# generation-7-electronics.net
KiCad netlist of a schematic drawn in EAGLE
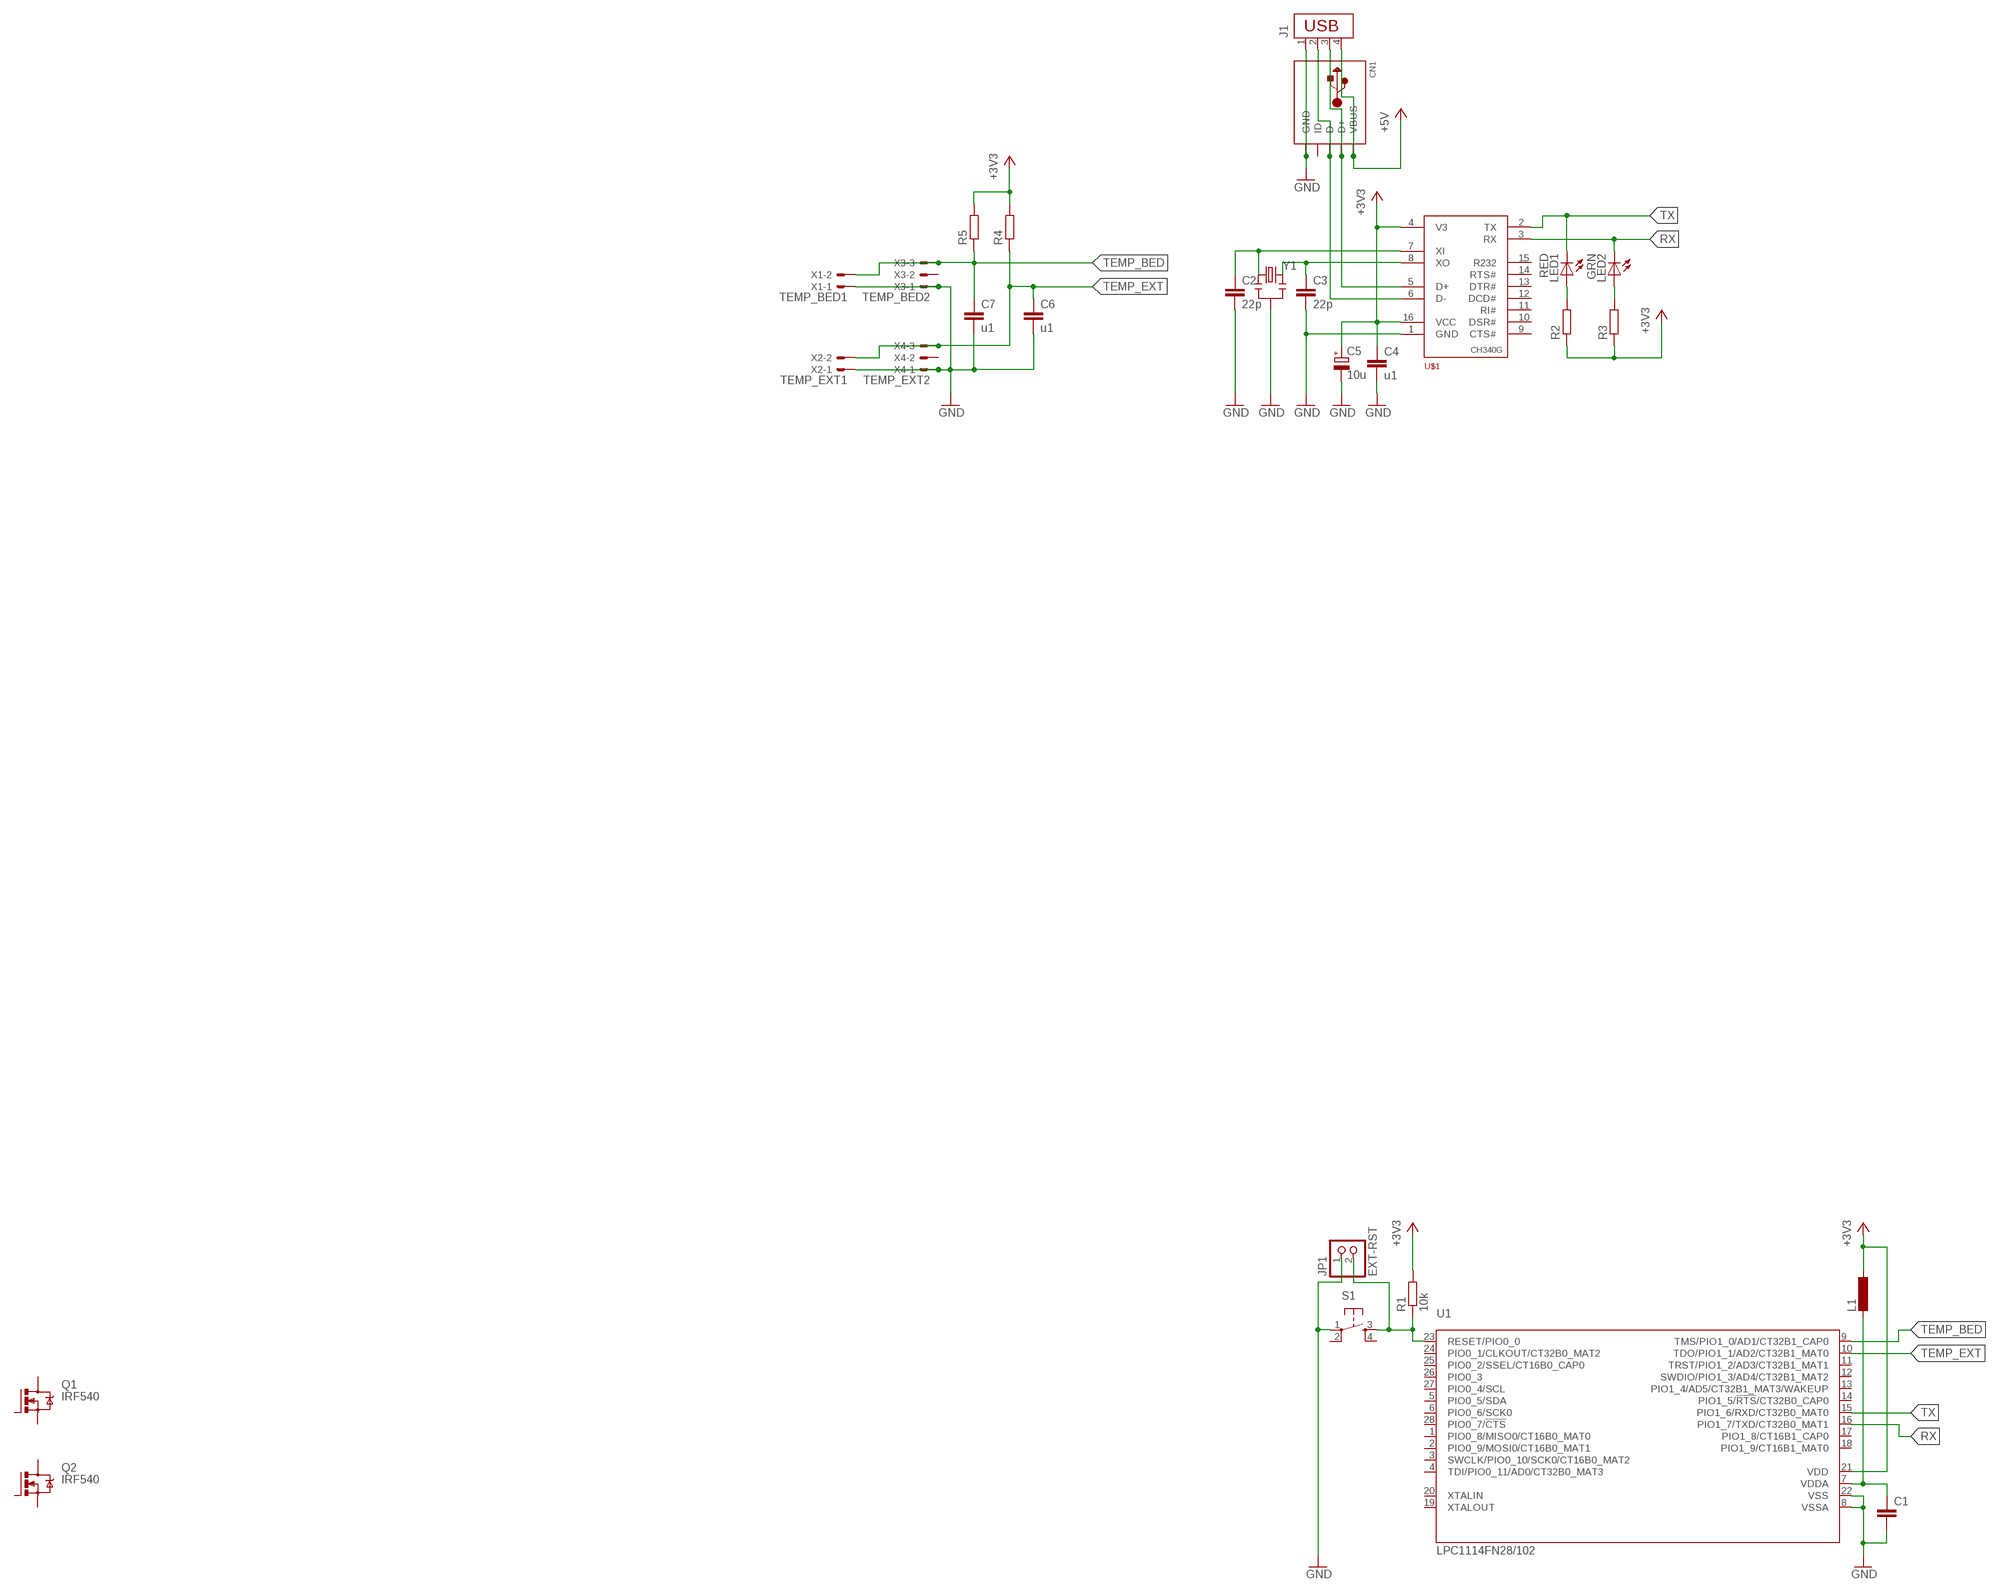
[diagram p0: schematic, sheet 1]

(export (version "E")
  (design (tool "Eeschema 10.0.6"))
  (components
    (comp (ref "C1")
      (value "C-EU025-025X050")
      (footprint "eagle-import:C025-025X050")
      (libsource (lib "eagle-import") (part "C-EU025-025X050"))
    )
    (comp (ref "C2")
      (value "22p")
      (footprint "eagle-import:C025-025X050")
      (libsource (lib "eagle-import") (part "C-EU025-025X050"))
    )
    (comp (ref "C3")
      (value "22p")
      (footprint "eagle-import:C025-025X050")
      (libsource (lib "eagle-import") (part "C-EU025-025X050"))
    )
    (comp (ref "C4")
      (value "u1")
      (footprint "eagle-import:C025-025X050")
      (libsource (lib "eagle-import") (part "C-EU025-025X050"))
    )
    (comp (ref "C5")
      (value "10u")
      (footprint "eagle-import:E2,5-6")
      (libsource (lib "eagle-import") (part "CPOL-EUE2.5-6"))
    )
    (comp (ref "C6")
      (value "u1")
      (footprint "eagle-import:C025-025X050")
      (libsource (lib "eagle-import") (part "C-EU025-025X050"))
    )
    (comp (ref "C7")
      (value "u1")
      (footprint "eagle-import:C025-025X050")
      (libsource (lib "eagle-import") (part "C-EU025-025X050"))
    )
    (comp (ref "CN1")
      (value "USBTHM")
      (footprint "eagle-import:USB-MINIB-THM")
      (libsource (lib "eagle-import") (part "USBTHM"))
    )
    (comp (ref "J1")
      (value "CON-USB-B")
      (footprint "eagle-import:USB-B")
      (libsource (lib "eagle-import") (part "CON-USB-B"))
    )
    (comp (ref "JP1")
      (value "EXT-RST")
      (footprint "eagle-import:1X02")
      (libsource (lib "eagle-import") (part "PINHD-1X2"))
    )
    (comp (ref "L1")
      (value "L-EU0207/2V")
      (footprint "eagle-import:0207_2V")
      (libsource (lib "eagle-import") (part "L-EU0207/2V"))
    )
    (comp (ref "LED1")
      (value "RED")
      (footprint "eagle-import:LED3MM")
      (libsource (lib "eagle-import") (part "LED3MM"))
    )
    (comp (ref "LED2")
      (value "GRN")
      (footprint "eagle-import:LED3MM")
      (libsource (lib "eagle-import") (part "LED3MM"))
    )
    (comp (ref "Q1")
      (value "IRF540")
      (footprint "eagle-import:TO220BV")
      (libsource (lib "eagle-import") (part "IRF540"))
    )
    (comp (ref "Q2")
      (value "IRF540")
      (footprint "eagle-import:TO220BV")
      (libsource (lib "eagle-import") (part "IRF540"))
    )
    (comp (ref "R1")
      (value "10k")
      (footprint "eagle-import:0204_7")
      (libsource (lib "eagle-import") (part "R-EU_0204/7"))
    )
    (comp (ref "R2")
      (value "R-EU_0204/7")
      (footprint "eagle-import:0204_7")
      (libsource (lib "eagle-import") (part "R-EU_0204/7"))
    )
    (comp (ref "R3")
      (value "R-EU_0204/7")
      (footprint "eagle-import:0204_7")
      (libsource (lib "eagle-import") (part "R-EU_0204/7"))
    )
    (comp (ref "R4")
      (value "R-EU_0204/7")
      (footprint "eagle-import:0204_7")
      (libsource (lib "eagle-import") (part "R-EU_0204/7"))
    )
    (comp (ref "R5")
      (value "R-EU_0204/7")
      (footprint "eagle-import:0204_7")
      (libsource (lib "eagle-import") (part "R-EU_0204/7"))
    )
    (comp (ref "S1")
      (value "TAC_SWITCHPTH")
      (footprint "eagle-import:TACTILE-PTH")
      (libsource (lib "eagle-import") (part "TAC_SWITCHPTH"))
    )
    (comp (ref "U$1")
      (value "CH340G")
      (footprint "eagle-import:SO16")
      (libsource (lib "eagle-import") (part "CH340G"))
    )
    (comp (ref "U1")
      (value "LPC1114FN28/102")
      (footprint "eagle-import:SOT117")
      (libsource (lib "eagle-import") (part "LPC1114FN28/102"))
    )
    (comp (ref "X1")
      (value "TEMP_BED1")
      (footprint "eagle-import:JST-XH-02-PACKAGE-LONG-PAD")
      (libsource (lib "eagle-import") (part "JST-XH-02-PIN-LONG-PAD"))
    )
    (comp (ref "X2")
      (value "TEMP_EXT1")
      (footprint "eagle-import:JST-XH-02-PACKAGE-LONG-PAD")
      (libsource (lib "eagle-import") (part "JST-XH-02-PIN-LONG-PAD"))
    )
    (comp (ref "X3")
      (value "TEMP_BED2")
      (footprint "eagle-import:JST-XH-03-PACKAGE-LONG-PAD")
      (libsource (lib "eagle-import") (part "JST-XH-03-PIN-LONG-PAD"))
    )
    (comp (ref "X4")
      (value "TEMP_EXT2")
      (footprint "eagle-import:JST-XH-03-PACKAGE-LONG-PAD")
      (libsource (lib "eagle-import") (part "JST-XH-03-PIN-LONG-PAD"))
    )
    (comp (ref "Y1")
      (value "RESONATORPTH")
      (footprint "eagle-import:RESONATOR-PTH")
      (libsource (lib "eagle-import") (part "RESONATORPTH"))
    )
  )
  (nets
    (net (code "1") (name "+3V3") (class "Default")
      (node (ref "C4") (pin "1") (pinfunction "1_1") (pintype "passive"))
      (node (ref "C5") (pin "+") (pinfunction "+_+") (pintype "passive"))
      (node (ref "L1") (pin "1") (pinfunction "1_1") (pintype "passive"))
      (node (ref "R1") (pin "2") (pinfunction "2_2") (pintype "passive"))
      (node (ref "R2") (pin "1") (pinfunction "1_1") (pintype "passive"))
      (node (ref "R3") (pin "1") (pinfunction "1_1") (pintype "passive"))
      (node (ref "R4") (pin "2") (pinfunction "2_2") (pintype "passive"))
      (node (ref "R5") (pin "2") (pinfunction "2_2") (pintype "passive"))
      (node (ref "U$1") (pin "16") (pinfunction "VCC_16") (pintype "bidirectional"))
      (node (ref "U$1") (pin "4") (pinfunction "V3_4") (pintype "bidirectional"))
      (node (ref "U1") (pin "21") (pinfunction "VDD_21") (pintype "power_in"))
    )
    (net (code "2") (name "+5V") (class "Default")
      (node (ref "CN1") (pin "VBUS") (pinfunction "VBUS_VBUS") (pintype "power_in"))
      (node (ref "J1") (pin "4") (pinfunction "4_4") (pintype "passive"))
    )
    (net (code "3") (name "GND") (class "Default")
      (node (ref "C1") (pin "2") (pinfunction "2_2") (pintype "passive"))
      (node (ref "C2") (pin "2") (pinfunction "2_2") (pintype "passive"))
      (node (ref "C3") (pin "2") (pinfunction "2_2") (pintype "passive"))
      (node (ref "C4") (pin "2") (pinfunction "2_2") (pintype "passive"))
      (node (ref "C5") (pin "-") (pinfunction "-_-") (pintype "passive"))
      (node (ref "C6") (pin "2") (pinfunction "2_2") (pintype "passive"))
      (node (ref "C7") (pin "2") (pinfunction "2_2") (pintype "passive"))
      (node (ref "CN1") (pin "GND") (pinfunction "GND_GND") (pintype "power_in"))
      (node (ref "J1") (pin "1") (pinfunction "1_1") (pintype "passive"))
      (node (ref "JP1") (pin "1") (pinfunction "1_1") (pintype "passive"))
      (node (ref "S1") (pin "1") (pinfunction "1_1") (pintype "passive"))
      (node (ref "U$1") (pin "1") (pinfunction "GND_1") (pintype "bidirectional"))
      (node (ref "U1") (pin "22") (pinfunction "VSS_22") (pintype "power_in"))
      (node (ref "U1") (pin "8") (pinfunction "VSSA_8") (pintype "power_in"))
      (node (ref "X1") (pin "1") (pinfunction "S_1") (pintype "passive"))
      (node (ref "X2") (pin "1") (pinfunction "S_1") (pintype "passive"))
      (node (ref "X3") (pin "1") (pinfunction "S_1") (pintype "passive"))
      (node (ref "X4") (pin "1") (pinfunction "S_1") (pintype "passive"))
      (node (ref "Y1") (pin "2") (pinfunction "2_2") (pintype "passive"))
    )
    (net (code "4") (name "Net-(LED1-PadA)") (class "Default")
      (node (ref "LED1") (pin "A") (pinfunction "A_A") (pintype "passive"))
      (node (ref "R2") (pin "2") (pinfunction "2_2") (pintype "passive"))
    )
    (net (code "5") (name "Net-(LED2-PadA)") (class "Default")
      (node (ref "LED2") (pin "A") (pinfunction "A_A") (pintype "passive"))
      (node (ref "R3") (pin "2") (pinfunction "2_2") (pintype "passive"))
    )
    (net (code "6") (name "Net-(U$1-D+)") (class "Default")
      (node (ref "CN1") (pin "D+") (pinfunction "D+_D+") (pintype "bidirectional"))
      (node (ref "J1") (pin "3") (pinfunction "3_3") (pintype "passive"))
      (node (ref "U$1") (pin "5") (pinfunction "D+_5") (pintype "bidirectional"))
    )
    (net (code "7") (name "Net-(U$1-D-)") (class "Default")
      (node (ref "CN1") (pin "D-") (pinfunction "D-_D-") (pintype "bidirectional"))
      (node (ref "J1") (pin "2") (pinfunction "2_2") (pintype "passive"))
      (node (ref "U$1") (pin "6") (pinfunction "D-_6") (pintype "bidirectional"))
    )
    (net (code "8") (name "Net-(U$1-XI)") (class "Default")
      (node (ref "C2") (pin "1") (pinfunction "1_1") (pintype "passive"))
      (node (ref "U$1") (pin "7") (pinfunction "XI_7") (pintype "bidirectional"))
      (node (ref "Y1") (pin "1") (pinfunction "1_1") (pintype "passive"))
    )
    (net (code "9") (name "Net-(U$1-XO)") (class "Default")
      (node (ref "C3") (pin "1") (pinfunction "1_1") (pintype "passive"))
      (node (ref "U$1") (pin "8") (pinfunction "XO_8") (pintype "bidirectional"))
      (node (ref "Y1") (pin "3") (pinfunction "3_3") (pintype "passive"))
    )
    (net (code "10") (name "Net-(U1-RESET{slash}PIO0_0)") (class "Default")
      (node (ref "JP1") (pin "2") (pinfunction "2_2") (pintype "passive"))
      (node (ref "R1") (pin "1") (pinfunction "1_1") (pintype "passive"))
      (node (ref "S1") (pin "3") (pinfunction "3_3") (pintype "passive"))
      (node (ref "U1") (pin "23") (pinfunction "RESET/PIO0_0_23") (pintype "bidirectional"))
    )
    (net (code "11") (name "Net-(U1-VDDA)") (class "Default")
      (node (ref "C1") (pin "1") (pinfunction "1_1") (pintype "passive"))
      (node (ref "L1") (pin "2") (pinfunction "2_2") (pintype "passive"))
      (node (ref "U1") (pin "7") (pinfunction "VDDA_7") (pintype "power_in"))
    )
    (net (code "12") (name "RX") (class "Default")
      (node (ref "LED2") (pin "K") (pinfunction "C_K") (pintype "passive"))
      (node (ref "U$1") (pin "3") (pinfunction "RX_3") (pintype "bidirectional"))
      (node (ref "U1") (pin "16") (pinfunction "PIO1_7/TXD/CT32B0_MAT1_16") (pintype "bidirectional"))
    )
    (net (code "13") (name "TEMP_BED") (class "Default")
      (node (ref "C7") (pin "1") (pinfunction "1_1") (pintype "passive"))
      (node (ref "R5") (pin "1") (pinfunction "1_1") (pintype "passive"))
      (node (ref "U1") (pin "9") (pinfunction "TMS/PIO1_0/AD1/CT32B1_CAP0_9") (pintype "bidirectional"))
      (node (ref "X1") (pin "2") (pinfunction "S_2") (pintype "passive"))
      (node (ref "X3") (pin "3") (pinfunction "S_3") (pintype "passive"))
    )
    (net (code "14") (name "TEMP_EXT") (class "Default")
      (node (ref "C6") (pin "1") (pinfunction "1_1") (pintype "passive"))
      (node (ref "R4") (pin "1") (pinfunction "1_1") (pintype "passive"))
      (node (ref "U1") (pin "10") (pinfunction "TDO/PIO1_1/AD2/CT32B1_MAT0_10") (pintype "bidirectional"))
      (node (ref "X2") (pin "2") (pinfunction "S_2") (pintype "passive"))
      (node (ref "X4") (pin "3") (pinfunction "S_3") (pintype "passive"))
    )
    (net (code "15") (name "TX") (class "Default")
      (node (ref "LED1") (pin "K") (pinfunction "C_K") (pintype "passive"))
      (node (ref "U$1") (pin "2") (pinfunction "TX_2") (pintype "bidirectional"))
      (node (ref "U1") (pin "15") (pinfunction "PIO1_6/RXD/CT32B0_MAT0_15") (pintype "bidirectional"))
    )
    (net (code "16") (name "unconnected-(CN1-PadID)") (class "Default")
      (node (ref "CN1") (pin "ID") (pinfunction "ID_ID") (pintype "bidirectional"))
    )
    (net (code "17") (name "unconnected-(Q1-PadD)") (class "Default")
      (node (ref "Q1") (pin "D") (pinfunction "D_D") (pintype "passive"))
    )
    (net (code "18") (name "unconnected-(Q1-PadG)") (class "Default")
      (node (ref "Q1") (pin "G") (pinfunction "G_G") (pintype "passive"))
    )
    (net (code "19") (name "unconnected-(Q1-PadS)") (class "Default")
      (node (ref "Q1") (pin "S") (pinfunction "S_S") (pintype "passive"))
    )
    (net (code "20") (name "unconnected-(Q2-PadD)") (class "Default")
      (node (ref "Q2") (pin "D") (pinfunction "D_D") (pintype "passive"))
    )
    (net (code "21") (name "unconnected-(Q2-PadG)") (class "Default")
      (node (ref "Q2") (pin "G") (pinfunction "G_G") (pintype "passive"))
    )
    (net (code "22") (name "unconnected-(Q2-PadS)") (class "Default")
      (node (ref "Q2") (pin "S") (pinfunction "S_S") (pintype "passive"))
    )
    (net (code "23") (name "unconnected-(S1-Pad2)") (class "Default")
      (node (ref "S1") (pin "2") (pinfunction "2_2") (pintype "passive"))
    )
    (net (code "24") (name "unconnected-(S1-Pad4)") (class "Default")
      (node (ref "S1") (pin "4") (pinfunction "4_4") (pintype "passive"))
    )
    (net (code "25") (name "unconnected-(U$1-CTS#-Pad9)") (class "Default")
      (node (ref "U$1") (pin "9") (pinfunction "CTS#_9") (pintype "bidirectional"))
    )
    (net (code "26") (name "unconnected-(U$1-DCD#-Pad12)") (class "Default")
      (node (ref "U$1") (pin "12") (pinfunction "DCD#_12") (pintype "bidirectional"))
    )
    (net (code "27") (name "unconnected-(U$1-DSR#-Pad10)") (class "Default")
      (node (ref "U$1") (pin "10") (pinfunction "DSR#_10") (pintype "bidirectional"))
    )
    (net (code "28") (name "unconnected-(U$1-DTR#-Pad13)") (class "Default")
      (node (ref "U$1") (pin "13") (pinfunction "DTR#_13") (pintype "bidirectional"))
    )
    (net (code "29") (name "unconnected-(U$1-R232-Pad15)") (class "Default")
      (node (ref "U$1") (pin "15") (pinfunction "R232_15") (pintype "bidirectional"))
    )
    (net (code "30") (name "unconnected-(U$1-RI#-Pad11)") (class "Default")
      (node (ref "U$1") (pin "11") (pinfunction "RI#_11") (pintype "bidirectional"))
    )
    (net (code "31") (name "unconnected-(U$1-RTS#-Pad14)") (class "Default")
      (node (ref "U$1") (pin "14") (pinfunction "RTS#_14") (pintype "bidirectional"))
    )
    (net (code "32") (name "unconnected-(U1-PIO0_1{slash}CLKOUT{slash}CT32B0_MAT2-Pad24)") (class "Default")
      (node (ref "U1") (pin "24") (pinfunction "PIO0_1/CLKOUT/CT32B0_MAT2_24") (pintype "bidirectional"))
    )
    (net (code "33") (name "unconnected-(U1-PIO0_2{slash}SSEL{slash}CT16B0_CAP0-Pad25)") (class "Default")
      (node (ref "U1") (pin "25") (pinfunction "PIO0_2/SSEL/CT16B0_CAP0_25") (pintype "bidirectional"))
    )
    (net (code "34") (name "unconnected-(U1-PIO0_3-Pad26)") (class "Default")
      (node (ref "U1") (pin "26") (pinfunction "PIO0_3_26") (pintype "bidirectional"))
    )
    (net (code "35") (name "unconnected-(U1-PIO0_4{slash}SCL-Pad27)") (class "Default")
      (node (ref "U1") (pin "27") (pinfunction "PIO0_4/SCL_27") (pintype "bidirectional"))
    )
    (net (code "36") (name "unconnected-(U1-PIO0_5{slash}SDA-Pad5)") (class "Default")
      (node (ref "U1") (pin "5") (pinfunction "PIO0_5/SDA_5") (pintype "bidirectional"))
    )
    (net (code "37") (name "unconnected-(U1-PIO0_6{slash}SCK0-Pad6)") (class "Default")
      (node (ref "U1") (pin "6") (pinfunction "PIO0_6/SCK0_6") (pintype "bidirectional"))
    )
    (net (code "38") (name "unconnected-(U1-PIO0_7{slash}~{CTS}-Pad28)") (class "Default")
      (node (ref "U1") (pin "28") (pinfunction "PIO0_7/~{CTS}_28") (pintype "bidirectional"))
    )
    (net (code "39") (name "unconnected-(U1-PIO0_8{slash}MISO0{slash}CT16B0_MAT0-Pad1)") (class "Default")
      (node (ref "U1") (pin "1") (pinfunction "PIO0_8/MISO0/CT16B0_MAT0_1") (pintype "bidirectional"))
    )
    (net (code "40") (name "unconnected-(U1-PIO0_9{slash}MOSI0{slash}CT16B0_MAT1-Pad2)") (class "Default")
      (node (ref "U1") (pin "2") (pinfunction "PIO0_9/MOSI0/CT16B0_MAT1_2") (pintype "bidirectional"))
    )
    (net (code "41") (name "unconnected-(U1-PIO1_4{slash}AD5{slash}CT32B1_MAT3{slash}WAKEUP-Pad13)") (class "Default")
      (node (ref "U1") (pin "13") (pinfunction "PIO1_4/AD5/CT32B1_MAT3/WAKEUP_13") (pintype "bidirectional"))
    )
    (net (code "42") (name "unconnected-(U1-PIO1_5{slash}~{RTS}{slash}CT32B0_CAP0-Pad14)") (class "Default")
      (node (ref "U1") (pin "14") (pinfunction "PIO1_5/~{RTS}/CT32B0_CAP0_14") (pintype "bidirectional"))
    )
    (net (code "43") (name "unconnected-(U1-PIO1_8{slash}CT16B1_CAP0-Pad17)") (class "Default")
      (node (ref "U1") (pin "17") (pinfunction "PIO1_8/CT16B1_CAP0_17") (pintype "bidirectional"))
    )
    (net (code "44") (name "unconnected-(U1-PIO1_9{slash}CT16B1_MAT0-Pad18)") (class "Default")
      (node (ref "U1") (pin "18") (pinfunction "PIO1_9/CT16B1_MAT0_18") (pintype "bidirectional"))
    )
    (net (code "45") (name "unconnected-(U1-SWCLK{slash}PIO0_10{slash}SCK0{slash}CT16B0_MAT2-Pad3)") (class "Default")
      (node (ref "U1") (pin "3") (pinfunction "SWCLK/PIO0_10/SCK0/CT16B0_MAT2_3") (pintype "bidirectional"))
    )
    (net (code "46") (name "unconnected-(U1-SWDIO{slash}PIO1_3{slash}AD4{slash}CT32B1_MAT2-Pad12)") (class "Default")
      (node (ref "U1") (pin "12") (pinfunction "SWDIO/PIO1_3/AD4/CT32B1_MAT2_12") (pintype "bidirectional"))
    )
    (net (code "47") (name "unconnected-(U1-TDI{slash}PIO0_11{slash}AD0{slash}CT32B0_MAT3-Pad4)") (class "Default")
      (node (ref "U1") (pin "4") (pinfunction "TDI/PIO0_11/AD0/CT32B0_MAT3_4") (pintype "bidirectional"))
    )
    (net (code "48") (name "unconnected-(U1-TRST{slash}PIO1_2{slash}AD3{slash}CT32B1_MAT1-Pad11)") (class "Default")
      (node (ref "U1") (pin "11") (pinfunction "TRST/PIO1_2/AD3/CT32B1_MAT1_11") (pintype "bidirectional"))
    )
    (net (code "49") (name "unconnected-(U1-XTALIN-Pad20)") (class "Default")
      (node (ref "U1") (pin "20") (pinfunction "XTALIN_20") (pintype "input"))
    )
    (net (code "50") (name "unconnected-(U1-XTALOUT-Pad19)") (class "Default")
      (node (ref "U1") (pin "19") (pinfunction "XTALOUT_19") (pintype "output"))
    )
    (net (code "51") (name "unconnected-(X3B-S-Pad2)") (class "Default")
      (node (ref "X3") (pin "2") (pinfunction "S_2") (pintype "passive"))
    )
    (net (code "52") (name "unconnected-(X4B-S-Pad2)") (class "Default")
      (node (ref "X4") (pin "2") (pinfunction "S_2") (pintype "passive"))
    )
  )
)
